# dsi_csi.net
KiCad netlist of a schematic drawn in Altium Designer
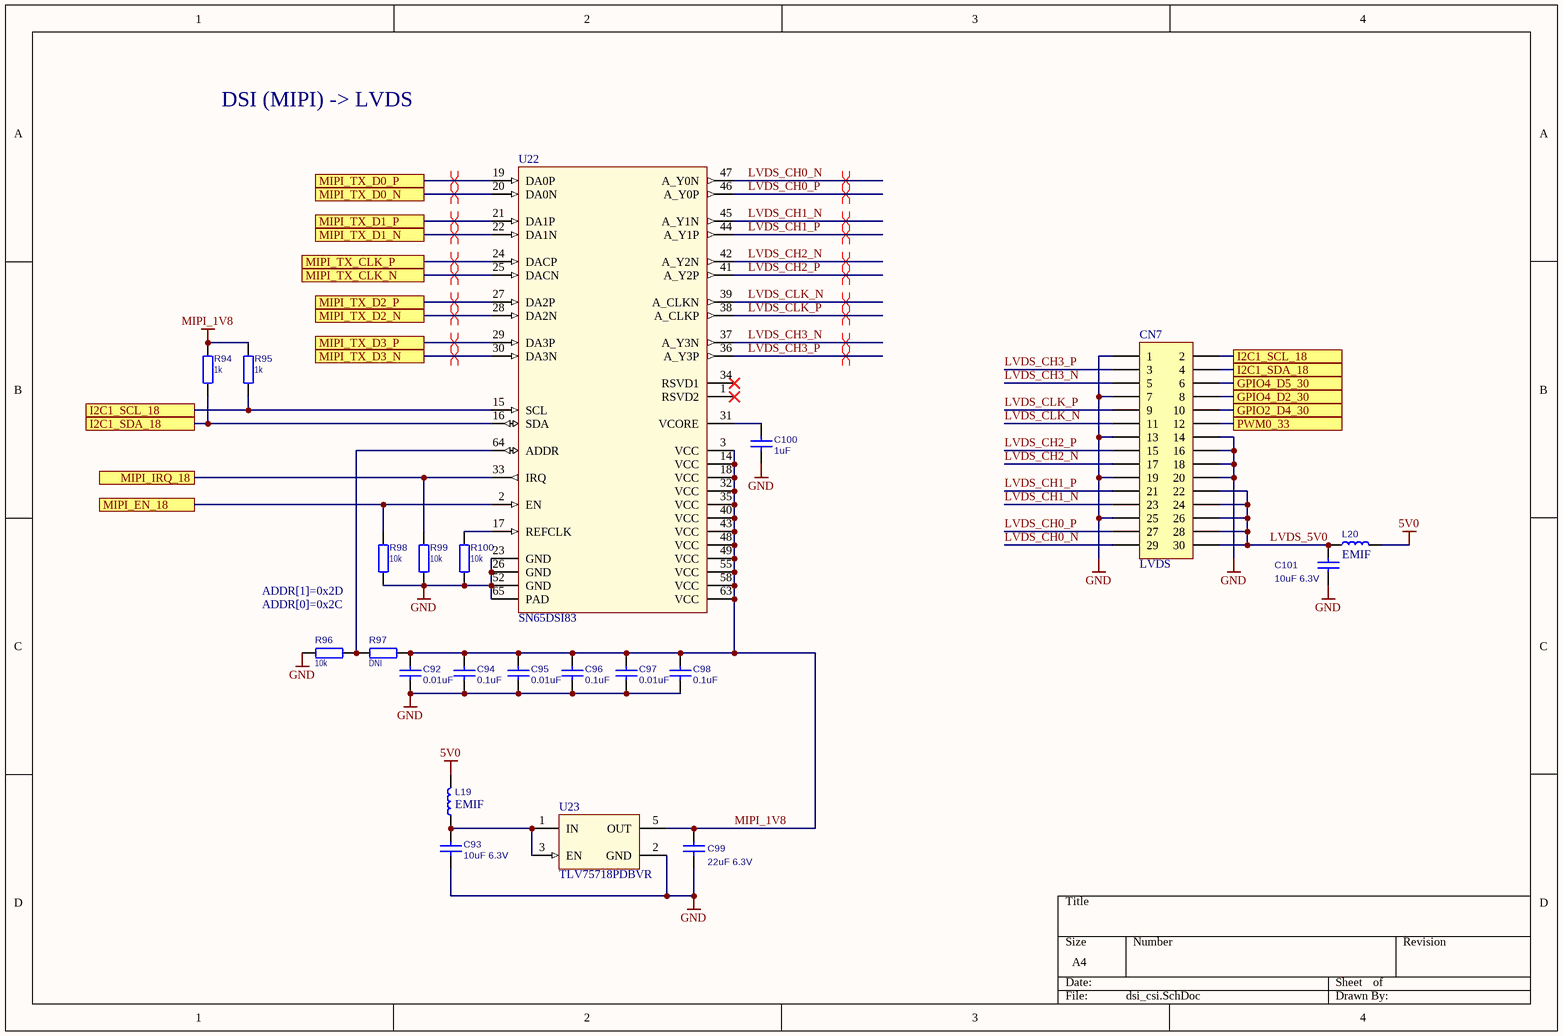
[diagram p0: dsi_csi.SchDoc]

(export (version "E")
  (design (tool "Eeschema 10.0.6"))
  (components
    (comp (ref "C92")
      (value "0.01uF")
      (footprint "Capacitors:C0603")
      (description "CAP_NPOL")
      (fields (field (name "Comment") "CL10B103KB8NNNC"))
      (libsource (lib "capacitors") (part "CAP_NPOL"))
    )
    (comp (ref "C93")
      (value "10uF 6.3V")
      (footprint "Capacitors:C0603")
      (description "CAP_NPOL")
      (fields (field (name "Comment") "CC0603MRX5R5BB106"))
      (libsource (lib "capacitors") (part "CAP_NPOL"))
    )
    (comp (ref "C94")
      (value "0.1uF")
      (footprint "Capacitors:C0603")
      (description "CAP_NPOL")
      (fields (field (name "Comment") "C1608X7R1H104K080AA"))
      (libsource (lib "capacitors") (part "CAP_NPOL"))
    )
    (comp (ref "C95")
      (value "0.01uF")
      (footprint "Capacitors:C0603")
      (description "CAP_NPOL")
      (fields (field (name "Comment") "CL10B103KB8NNNC"))
      (libsource (lib "capacitors") (part "CAP_NPOL"))
    )
    (comp (ref "C96")
      (value "0.1uF")
      (footprint "Capacitors:C0603")
      (description "CAP_NPOL")
      (fields (field (name "Comment") "C1608X7R1H104K080AA"))
      (libsource (lib "capacitors") (part "CAP_NPOL"))
    )
    (comp (ref "C97")
      (value "0.01uF")
      (footprint "Capacitors:C0603")
      (description "CAP_NPOL")
      (fields (field (name "Comment") "CL10B103KB8NNNC"))
      (libsource (lib "capacitors") (part "CAP_NPOL"))
    )
    (comp (ref "C98")
      (value "0.1uF")
      (footprint "Capacitors:C0603")
      (description "CAP_NPOL")
      (fields (field (name "Comment") "C1608X7R1H104K080AA"))
      (libsource (lib "capacitors") (part "CAP_NPOL"))
    )
    (comp (ref "C99")
      (value "22uF 6.3V")
      (footprint "C0805")
      (description "CAP_NPOL")
      (fields (field (name "Comment") "CL21A226MQQNNNE"))
      (libsource (lib "capacitors") (part "CAP_NPOL"))
    )
    (comp (ref "C100")
      (value "1uF")
      (footprint "Capacitors:C0603")
      (description "CAP_NPOL")
      (fields (field (name "Comment") "GRM188R61H105KAALD"))
      (libsource (lib "capacitors") (part "CAP_NPOL"))
    )
    (comp (ref "C101")
      (value "10uF 6.3V")
      (footprint "Capacitors:C0603")
      (description "CAP_NPOL")
      (fields (field (name "Comment") "CC0603MRX5R5BB106"))
      (libsource (lib "capacitors") (part "CAP_NPOL"))
    )
    (comp (ref "CN7")
      (value "LVDS")
      (footprint "DF13EA-30DP-1.25V")
      (description "Header, 15-Pin, Dual row")
      (fields (field (name "PUBLISHER") "Altium Limited"))
      (libsource (lib "HDR") (part "HDR 15X2"))
    )
    (comp (ref "L19")
      (value "EMIF")
      (footprint "IND0603")
      (description "IND_WO_IRON")
      (fields (field (name "Comment") "BLM18AG102SN1D"))
      (libsource (lib "") (part "IND_WO_IRON_1"))
    )
    (comp (ref "L20")
      (value "EMIF")
      (footprint "IND0805")
      (description "IND_WO_IRON")
      (fields (field (name "Comment") "BLM21PG221SN1D"))
      (libsource (lib "inductors") (part "IND_WO_IRON"))
    )
    (comp (ref "R94")
      (value "1k")
      (footprint "R0603")
      (description "RES")
      (libsource (lib "resistors") (part "RESISTOR"))
    )
    (comp (ref "R95")
      (value "1k")
      (footprint "R0603")
      (description "RES")
      (libsource (lib "resistors") (part "RESISTOR"))
    )
    (comp (ref "R96")
      (value "10k")
      (footprint "R0603")
      (description "RES")
      (libsource (lib "resistors") (part "RESISTOR"))
    )
    (comp (ref "R97")
      (value "DNI")
      (footprint "R0603")
      (description "RES")
      (libsource (lib "resistors") (part "RESISTOR"))
    )
    (comp (ref "R98")
      (value "10k")
      (footprint "R0603")
      (description "RES")
      (libsource (lib "resistors") (part "RESISTOR"))
    )
    (comp (ref "R99")
      (value "10k")
      (footprint "R0603")
      (description "RES")
      (libsource (lib "resistors") (part "RESISTOR"))
    )
    (comp (ref "R100")
      (value "10k")
      (footprint "R0603")
      (description "RES")
      (libsource (lib "resistors") (part "RESISTOR"))
    )
    (comp (ref "U22")
      (value "SN65DSI83")
      (footprint "HPM064_N")
      (description "Single-Channel MIPI® DSI to Single-Link LVDS Bridge")
      (libsource (lib "SN65DSI83") (part "SN65DSI83"))
    )
    (comp (ref "U23")
      (value "TLV75718PDBVR")
      (footprint "SOT-23-5")
      (description "Capacitor-Free, 300-mA, Low-Dropout Regulator with Foldback Current Limit for Portable Devices")
      (libsource (lib "TLV733P") (part "TLV733P"))
    )
  )
  (nets
    (net (code "1") (name "/GPIO2_D4_30") (class "Default")
      (node (ref "CN7") (pin "10") (pinfunction "10_10") (pintype "passive"))
    )
    (net (code "2") (name "/GPIO4_D2_30") (class "Default")
      (node (ref "CN7") (pin "8") (pinfunction "8_8") (pintype "passive"))
    )
    (net (code "3") (name "/GPIO4_D5_30") (class "Default")
      (node (ref "CN7") (pin "6") (pinfunction "6_6") (pintype "passive"))
    )
    (net (code "4") (name "/I2C1_SCL_18") (class "Default")
      (node (ref "CN7") (pin "2") (pinfunction "2_2") (pintype "passive"))
      (node (ref "R95") (pin "2") (pinfunction "2_2") (pintype "passive"))
      (node (ref "U22") (pin "15") (pinfunction "SCL_15") (pintype "input"))
    )
    (net (code "5") (name "/I2C1_SDA_18") (class "Default")
      (node (ref "CN7") (pin "4") (pinfunction "4_4") (pintype "passive"))
      (node (ref "R94") (pin "2") (pinfunction "2_2") (pintype "passive"))
      (node (ref "U22") (pin "16") (pinfunction "SDA_16") (pintype "bidirectional"))
    )
    (net (code "6") (name "/LVDS_5V0") (class "Default")
      (node (ref "C101") (pin "1") (pinfunction "1_1") (pintype "passive"))
      (node (ref "CN7") (pin "22") (pinfunction "22_22") (pintype "passive"))
      (node (ref "CN7") (pin "24") (pinfunction "24_24") (pintype "passive"))
      (node (ref "CN7") (pin "26") (pinfunction "26_26") (pintype "passive"))
      (node (ref "CN7") (pin "28") (pinfunction "28_28") (pintype "passive"))
      (node (ref "CN7") (pin "30") (pinfunction "30_30") (pintype "passive"))
      (node (ref "L20") (pin "2") (pintype "passive"))
    )
    (net (code "7") (name "/LVDS_CH0_N") (class "Default")
      (node (ref "CN7") (pin "29") (pinfunction "29_29") (pintype "passive"))
      (node (ref "U22") (pin "47") (pinfunction "A_Y0N_47") (pintype "output"))
    )
    (net (code "8") (name "/LVDS_CH0_P") (class "Default")
      (node (ref "CN7") (pin "27") (pinfunction "27_27") (pintype "passive"))
      (node (ref "U22") (pin "46") (pinfunction "A_Y0P_46") (pintype "output"))
    )
    (net (code "9") (name "/LVDS_CH1_N") (class "Default")
      (node (ref "CN7") (pin "23") (pinfunction "23_23") (pintype "passive"))
      (node (ref "U22") (pin "45") (pinfunction "A_Y1N_45") (pintype "output"))
    )
    (net (code "10") (name "/LVDS_CH1_P") (class "Default")
      (node (ref "CN7") (pin "21") (pinfunction "21_21") (pintype "passive"))
      (node (ref "U22") (pin "44") (pinfunction "A_Y1P_44") (pintype "output"))
    )
    (net (code "11") (name "/LVDS_CH2_N") (class "Default")
      (node (ref "CN7") (pin "17") (pinfunction "17_17") (pintype "passive"))
      (node (ref "U22") (pin "42") (pinfunction "A_Y2N_42") (pintype "output"))
    )
    (net (code "12") (name "/LVDS_CH2_P") (class "Default")
      (node (ref "CN7") (pin "15") (pinfunction "15_15") (pintype "passive"))
      (node (ref "U22") (pin "41") (pinfunction "A_Y2P_41") (pintype "output"))
    )
    (net (code "13") (name "/LVDS_CH3_N") (class "Default")
      (node (ref "CN7") (pin "5") (pinfunction "5_5") (pintype "passive"))
      (node (ref "U22") (pin "37") (pinfunction "A_Y3N_37") (pintype "output"))
    )
    (net (code "14") (name "/LVDS_CH3_P") (class "Default")
      (node (ref "CN7") (pin "3") (pinfunction "3_3") (pintype "passive"))
      (node (ref "U22") (pin "36") (pinfunction "A_Y3P_36") (pintype "output"))
    )
    (net (code "15") (name "/LVDS_CLK_N") (class "Default")
      (node (ref "CN7") (pin "11") (pinfunction "11_11") (pintype "passive"))
      (node (ref "U22") (pin "39") (pinfunction "A_CLKN_39") (pintype "output"))
    )
    (net (code "16") (name "/LVDS_CLK_P") (class "Default")
      (node (ref "CN7") (pin "9") (pinfunction "9_9") (pintype "passive"))
      (node (ref "U22") (pin "38") (pinfunction "A_CLKP_38") (pintype "output"))
    )
    (net (code "17") (name "/MIPI_EN_18") (class "Default")
      (node (ref "R98") (pin "2") (pinfunction "2_2") (pintype "passive"))
      (node (ref "U22") (pin "2") (pinfunction "EN_2") (pintype "input"))
    )
    (net (code "18") (name "/MIPI_IRQ_18") (class "Default")
      (node (ref "R99") (pin "2") (pinfunction "2_2") (pintype "passive"))
      (node (ref "U22") (pin "33") (pinfunction "IRQ_33") (pintype "output"))
    )
    (net (code "19") (name "/MIPI_TX_CLK_N") (class "Default")
      (node (ref "U22") (pin "25") (pinfunction "DACN_25") (pintype "input"))
    )
    (net (code "20") (name "/MIPI_TX_CLK_P") (class "Default")
      (node (ref "U22") (pin "24") (pinfunction "DACP_24") (pintype "input"))
    )
    (net (code "21") (name "/MIPI_TX_D0_N") (class "Default")
      (node (ref "U22") (pin "20") (pinfunction "DA0N_20") (pintype "input"))
    )
    (net (code "22") (name "/MIPI_TX_D0_P") (class "Default")
      (node (ref "U22") (pin "19") (pinfunction "DA0P_19") (pintype "input"))
    )
    (net (code "23") (name "/MIPI_TX_D1_N") (class "Default")
      (node (ref "U22") (pin "22") (pinfunction "DA1N_22") (pintype "input"))
    )
    (net (code "24") (name "/MIPI_TX_D1_P") (class "Default")
      (node (ref "U22") (pin "21") (pinfunction "DA1P_21") (pintype "input"))
    )
    (net (code "25") (name "/MIPI_TX_D2_N") (class "Default")
      (node (ref "U22") (pin "28") (pinfunction "DA2N_28") (pintype "input"))
    )
    (net (code "26") (name "/MIPI_TX_D2_P") (class "Default")
      (node (ref "U22") (pin "27") (pinfunction "DA2P_27") (pintype "input"))
    )
    (net (code "27") (name "/MIPI_TX_D3_N") (class "Default")
      (node (ref "U22") (pin "30") (pinfunction "DA3N_30") (pintype "input"))
    )
    (net (code "28") (name "/MIPI_TX_D3_P") (class "Default")
      (node (ref "U22") (pin "29") (pinfunction "DA3P_29") (pintype "input"))
    )
    (net (code "29") (name "/PWM0_33") (class "Default")
      (node (ref "CN7") (pin "12") (pinfunction "12_12") (pintype "passive"))
    )
    (net (code "30") (name "5V0") (class "Default")
      (node (ref "L19") (pin "2") (pintype "passive"))
      (node (ref "L20") (pin "1") (pintype "passive"))
    )
    (net (code "31") (name "GND") (class "Default")
      (node (ref "C100") (pin "1") (pinfunction "1_1") (pintype "passive"))
      (node (ref "C101") (pin "2") (pinfunction "2_2") (pintype "passive"))
      (node (ref "C92") (pin "2") (pinfunction "2_2") (pintype "passive"))
      (node (ref "C93") (pin "2") (pinfunction "2_2") (pintype "passive"))
      (node (ref "C94") (pin "1") (pinfunction "1_1") (pintype "passive"))
      (node (ref "C95") (pin "2") (pinfunction "2_2") (pintype "passive"))
      (node (ref "C96") (pin "1") (pinfunction "1_1") (pintype "passive"))
      (node (ref "C97") (pin "2") (pinfunction "2_2") (pintype "passive"))
      (node (ref "C98") (pin "1") (pinfunction "1_1") (pintype "passive"))
      (node (ref "C99") (pin "1") (pinfunction "1_1") (pintype "passive"))
      (node (ref "CN7") (pin "1") (pinfunction "1_1") (pintype "passive"))
      (node (ref "CN7") (pin "13") (pinfunction "13_13") (pintype "passive"))
      (node (ref "CN7") (pin "14") (pinfunction "14_14") (pintype "passive"))
      (node (ref "CN7") (pin "16") (pinfunction "16_16") (pintype "passive"))
      (node (ref "CN7") (pin "18") (pinfunction "18_18") (pintype "passive"))
      (node (ref "CN7") (pin "19") (pinfunction "19_19") (pintype "passive"))
      (node (ref "CN7") (pin "20") (pinfunction "20_20") (pintype "passive"))
      (node (ref "CN7") (pin "25") (pinfunction "25_25") (pintype "passive"))
      (node (ref "CN7") (pin "7") (pinfunction "7_7") (pintype "passive"))
      (node (ref "R100") (pin "1") (pinfunction "1_1") (pintype "passive"))
      (node (ref "R96") (pin "1") (pinfunction "1_1") (pintype "passive"))
      (node (ref "R98") (pin "1") (pinfunction "1_1") (pintype "passive"))
      (node (ref "R99") (pin "1") (pinfunction "1_1") (pintype "passive"))
      (node (ref "U22") (pin "23") (pinfunction "GND_23") (pintype "power_in"))
      (node (ref "U22") (pin "26") (pinfunction "GND_26") (pintype "power_in"))
      (node (ref "U22") (pin "52") (pinfunction "GND_52") (pintype "power_in"))
      (node (ref "U22") (pin "65") (pinfunction "PAD_65") (pintype "power_in"))
      (node (ref "U23") (pin "2") (pinfunction "GND_2") (pintype "power_in"))
    )
    (net (code "32") (name "MIPI_1V8") (class "Default")
      (node (ref "C92") (pin "1") (pinfunction "1_1") (pintype "passive"))
      (node (ref "C94") (pin "2") (pinfunction "2_2") (pintype "passive"))
      (node (ref "C95") (pin "1") (pinfunction "1_1") (pintype "passive"))
      (node (ref "C96") (pin "2") (pinfunction "2_2") (pintype "passive"))
      (node (ref "C97") (pin "1") (pinfunction "1_1") (pintype "passive"))
      (node (ref "C98") (pin "2") (pinfunction "2_2") (pintype "passive"))
      (node (ref "C99") (pin "2") (pinfunction "2_2") (pintype "passive"))
      (node (ref "R94") (pin "1") (pinfunction "1_1") (pintype "passive"))
      (node (ref "R95") (pin "1") (pinfunction "1_1") (pintype "passive"))
      (node (ref "R97") (pin "2") (pinfunction "2_2") (pintype "passive"))
      (node (ref "U22") (pin "14") (pinfunction "VCC_14") (pintype "power_in"))
      (node (ref "U22") (pin "18") (pinfunction "VCC_18") (pintype "power_in"))
      (node (ref "U22") (pin "3") (pinfunction "VCC_3") (pintype "power_in"))
      (node (ref "U22") (pin "32") (pinfunction "VCC_32") (pintype "power_in"))
      (node (ref "U22") (pin "35") (pinfunction "VCC_35") (pintype "power_in"))
      (node (ref "U22") (pin "40") (pinfunction "VCC_40") (pintype "power_in"))
      (node (ref "U22") (pin "43") (pinfunction "VCC_43") (pintype "power_in"))
      (node (ref "U22") (pin "48") (pinfunction "VCC_48") (pintype "power_in"))
      (node (ref "U22") (pin "49") (pinfunction "VCC_49") (pintype "power_in"))
      (node (ref "U22") (pin "55") (pinfunction "VCC_55") (pintype "power_in"))
      (node (ref "U22") (pin "58") (pinfunction "VCC_58") (pintype "power_in"))
      (node (ref "U22") (pin "63") (pinfunction "VCC_63") (pintype "power_in"))
      (node (ref "U23") (pin "5") (pinfunction "OUT_5") (pintype "power_in"))
    )
    (net (code "33") (name "Net-(U22-ADDR)") (class "Default")
      (node (ref "R96") (pin "2") (pinfunction "2_2") (pintype "passive"))
      (node (ref "R97") (pin "1") (pinfunction "1_1") (pintype "passive"))
      (node (ref "U22") (pin "64") (pinfunction "ADDR_64") (pintype "bidirectional"))
    )
    (net (code "34") (name "Net-(U22-REFCLK)") (class "Default")
      (node (ref "R100") (pin "2") (pinfunction "2_2") (pintype "passive"))
      (node (ref "U22") (pin "17") (pinfunction "REFCLK_17") (pintype "input"))
    )
    (net (code "35") (name "Net-(U22-VCORE)") (class "Default")
      (node (ref "C100") (pin "2") (pinfunction "2_2") (pintype "passive"))
      (node (ref "U22") (pin "31") (pinfunction "VCORE_31") (pintype "power_in"))
    )
    (net (code "36") (name "Net-(U23-EN)") (class "Default")
      (node (ref "C93") (pin "1") (pinfunction "1_1") (pintype "passive"))
      (node (ref "L19") (pin "1") (pintype "passive"))
      (node (ref "U23") (pin "1") (pinfunction "IN_1") (pintype "power_in"))
      (node (ref "U23") (pin "3") (pinfunction "EN_3") (pintype "input"))
    )
    (net (code "37") (name "unconnected-(U22-RSVD1-Pad34)") (class "Default")
      (node (ref "U22") (pin "34") (pinfunction "RSVD1_34") (pintype "passive+no_connect"))
    )
    (net (code "38") (name "unconnected-(U22-RSVD2-Pad1)") (class "Default")
      (node (ref "U22") (pin "1") (pinfunction "RSVD2_1") (pintype "passive+no_connect"))
    )
  )
)
